# FX_MCU.net
KiCad netlist of a schematic drawn in Altium Designer
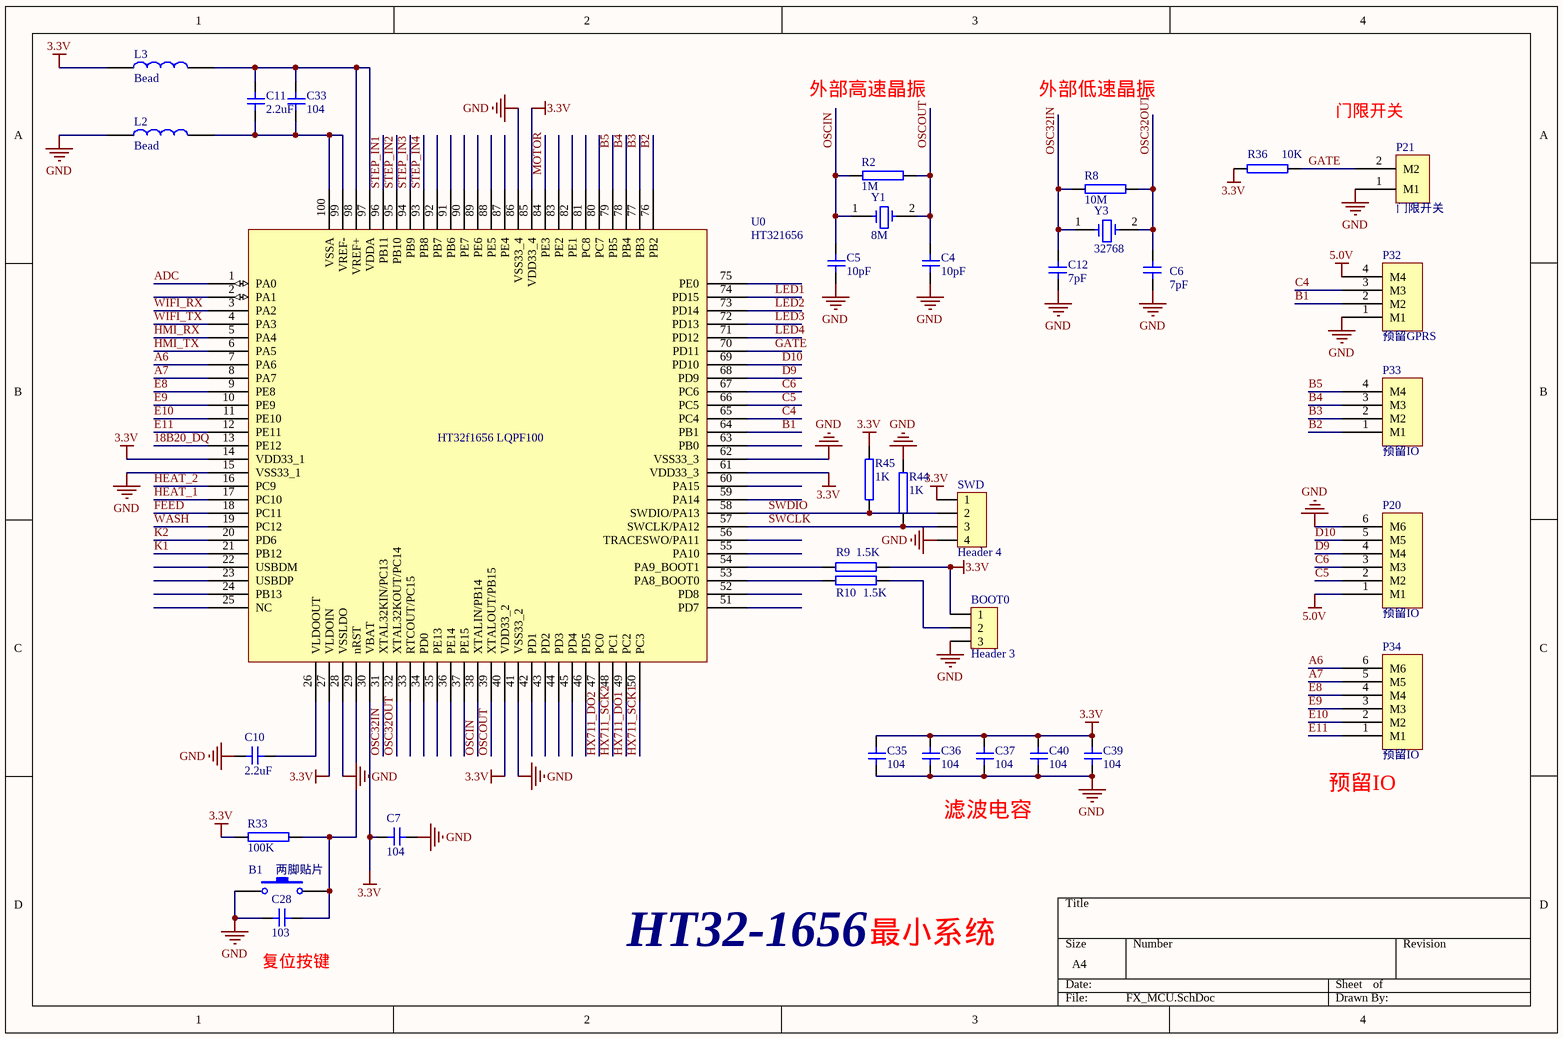
[diagram p0: FX_MCU.SchDoc]

(export (version "E")
  (design (tool "Eeschema 10.0.6"))
  (components
    (comp (ref "B1") (value "两脚贴片") (footprint "贴片按键") (libsource (lib "窝牛器件封装") (part "Key(两脚贴片)")))
    (comp (ref "BOOT0")
      (value "Header 3")
      (footprint "Header 3")
      (libsource (lib "窝牛器件封装") (part "Header 3"))
    )
    (comp (ref "C4") (value "10pF") (footprint "0805C") (libsource (lib "窝牛器件封装") (part "C1")))
    (comp (ref "C5") (value "10pF") (footprint "0805C") (libsource (lib "窝牛器件封装") (part "C1")))
    (comp (ref "C6") (value "7pF") (footprint "0805C") (libsource (lib "窝牛器件封装") (part "C1")))
    (comp (ref "C7") (value "104") (footprint "0805C") (libsource (lib "窝牛器件封装") (part "C1")))
    (comp (ref "C10") (value "2.2uF") (footprint "0805C") (libsource (lib "窝牛器件封装") (part "C1")))
    (comp (ref "C11") (value "2.2uF") (footprint "0805C") (libsource (lib "窝牛器件封装") (part "C1")))
    (comp (ref "C12") (value "7pF") (footprint "0805C") (libsource (lib "窝牛器件封装") (part "C1")))
    (comp (ref "C28") (value "103") (footprint "0805C") (libsource (lib "窝牛器件封装") (part "C1")))
    (comp (ref "C33") (value "104") (footprint "0805C") (libsource (lib "窝牛器件封装") (part "C1")))
    (comp (ref "C35") (value "104") (footprint "0805C") (libsource (lib "窝牛器件封装") (part "C1")))
    (comp (ref "C36") (value "104") (footprint "0805C") (libsource (lib "窝牛器件封装") (part "C1")))
    (comp (ref "C37") (value "104") (footprint "0805C") (libsource (lib "窝牛器件封装") (part "C1")))
    (comp (ref "C39") (value "104") (footprint "0805C") (libsource (lib "窝牛器件封装") (part "C1")))
    (comp (ref "C40") (value "104") (footprint "0805C") (libsource (lib "窝牛器件封装") (part "C1")))
    (comp (ref "L2") (value "Bead") (footprint "0805L") (libsource (lib "窝牛器件封装") (part "L1")))
    (comp (ref "L3") (value "Bead") (footprint "0805L") (libsource (lib "窝牛器件封装") (part "L1")))
    (comp (ref "P20")
      (value "预留IO")
      (footprint "接线端子(小)-6PIN")
      (libsource (lib "窝牛器件封装") (part "接线端子(小)-6PIN"))
    )
    (comp (ref "P21")
      (value "门限开关")
      (footprint "接线端子(小)-2PIN")
      (libsource (lib "窝牛器件封装") (part "接线端子(小)-2PIN"))
    )
    (comp (ref "P32")
      (value "预留GPRS")
      (footprint "接线端子(小)-4PIN")
      (libsource (lib "窝牛器件封装") (part "接线端子(小)-4PIN"))
    )
    (comp (ref "P33")
      (value "预留IO")
      (footprint "接线端子(小)-4PIN")
      (libsource (lib "窝牛器件封装") (part "接线端子(小)-4PIN"))
    )
    (comp (ref "P34")
      (value "预留IO")
      (footprint "接线端子(小)-6PIN")
      (libsource (lib "窝牛器件封装") (part "接线端子(小)-6PIN"))
    )
    (comp (ref "R2") (value "1M") (footprint "0805R") (libsource (lib "窝牛器件封装") (part "R1")))
    (comp (ref "R8") (value "10M") (footprint "0805R") (libsource (lib "窝牛器件封装") (part "R1")))
    (comp (ref "R9") (value "1.5K") (footprint "0805R") (libsource (lib "窝牛器件封装") (part "R1")))
    (comp (ref "R10") (value "1.5K") (footprint "0805R") (libsource (lib "窝牛器件封装") (part "R1")))
    (comp (ref "R33") (value "100K") (footprint "0805R") (libsource (lib "窝牛器件封装") (part "R1")))
    (comp (ref "R36") (value "10K") (footprint "0805R") (libsource (lib "窝牛器件封装") (part "R1")))
    (comp (ref "R44") (value "1K") (footprint "0805R") (libsource (lib "窝牛器件封装") (part "R1")))
    (comp (ref "R45") (value "1K") (footprint "0805R") (libsource (lib "窝牛器件封装") (part "R1")))
    (comp (ref "SWD") (value "Header 4") (footprint "Header 4") (libsource (lib "窝牛器件封装") (part "Header 4")))
    (comp (ref "U0") (value "HT321656") (footprint "LQFP100") (libsource (lib "devil") (part "HT321656")))
    (comp (ref "Y1") (value "8M") (footprint "22M(晶振)") (libsource (lib "窝牛器件封装") (part "XTAL")))
    (comp (ref "Y3") (value "32768") (footprint "XTAL") (libsource (lib "窝牛器件封装") (part "XTAL")))
  )
  (nets
    (net (code "1") (name "/18B20_DQ") (class "Default")
      (node (ref "U0") (pin "13") (pinfunction "PE12_13") (pintype "passive"))
    )
    (net (code "2") (name "/A6") (class "Default")
      (node (ref "P34") (pin "6") (pinfunction "M6_6") (pintype "passive"))
      (node (ref "U0") (pin "7") (pinfunction "PA6_7") (pintype "passive"))
    )
    (net (code "3") (name "/A7") (class "Default")
      (node (ref "P34") (pin "5") (pinfunction "M5_5") (pintype "passive"))
      (node (ref "U0") (pin "8") (pinfunction "PA7_8") (pintype "passive"))
    )
    (net (code "4") (name "/ADC") (class "Default")
      (node (ref "U0") (pin "1") (pinfunction "PA0_1") (pintype "bidirectional"))
    )
    (net (code "5") (name "/B1") (class "Default")
      (node (ref "P32") (pin "2") (pinfunction "M2_2") (pintype "passive"))
      (node (ref "U0") (pin "64") (pinfunction "PB1_64") (pintype "passive"))
    )
    (net (code "6") (name "/B2") (class "Default")
      (node (ref "P33") (pin "1") (pinfunction "M1_1") (pintype "passive"))
      (node (ref "U0") (pin "76") (pinfunction "PB2_76") (pintype "passive"))
    )
    (net (code "7") (name "/B3") (class "Default")
      (node (ref "P33") (pin "2") (pinfunction "M2_2") (pintype "passive"))
      (node (ref "U0") (pin "77") (pinfunction "PB3_77") (pintype "passive"))
    )
    (net (code "8") (name "/B4") (class "Default")
      (node (ref "P33") (pin "3") (pinfunction "M3_3") (pintype "passive"))
      (node (ref "U0") (pin "78") (pinfunction "PB4_78") (pintype "passive"))
    )
    (net (code "9") (name "/B5") (class "Default")
      (node (ref "P33") (pin "4") (pinfunction "M4_4") (pintype "passive"))
      (node (ref "U0") (pin "79") (pinfunction "PB5_79") (pintype "passive"))
    )
    (net (code "10") (name "/C4") (class "Default")
      (node (ref "P32") (pin "3") (pinfunction "M3_3") (pintype "passive"))
      (node (ref "U0") (pin "65") (pinfunction "PC4_65") (pintype "passive"))
    )
    (net (code "11") (name "/C5") (class "Default")
      (node (ref "P20") (pin "2") (pinfunction "M2_2") (pintype "passive"))
      (node (ref "U0") (pin "66") (pinfunction "PC5_66") (pintype "passive"))
    )
    (net (code "12") (name "/C6") (class "Default")
      (node (ref "P20") (pin "3") (pinfunction "M3_3") (pintype "passive"))
      (node (ref "U0") (pin "67") (pinfunction "PC6_67") (pintype "passive"))
    )
    (net (code "13") (name "/D9") (class "Default")
      (node (ref "P20") (pin "4") (pinfunction "M4_4") (pintype "passive"))
      (node (ref "U0") (pin "68") (pinfunction "PD9_68") (pintype "passive"))
    )
    (net (code "14") (name "/D10") (class "Default")
      (node (ref "P20") (pin "5") (pinfunction "M5_5") (pintype "passive"))
      (node (ref "U0") (pin "69") (pinfunction "PD10_69") (pintype "passive"))
    )
    (net (code "15") (name "/E8") (class "Default")
      (node (ref "P34") (pin "4") (pinfunction "M4_4") (pintype "passive"))
      (node (ref "U0") (pin "9") (pinfunction "PE8_9") (pintype "passive"))
    )
    (net (code "16") (name "/E9") (class "Default")
      (node (ref "P34") (pin "3") (pinfunction "M3_3") (pintype "passive"))
      (node (ref "U0") (pin "10") (pinfunction "PE9_10") (pintype "passive"))
    )
    (net (code "17") (name "/E10") (class "Default")
      (node (ref "P34") (pin "2") (pinfunction "M2_2") (pintype "passive"))
      (node (ref "U0") (pin "11") (pinfunction "PE10_11") (pintype "passive"))
    )
    (net (code "18") (name "/E11") (class "Default")
      (node (ref "P34") (pin "1") (pinfunction "M1_1") (pintype "passive"))
      (node (ref "U0") (pin "12") (pinfunction "PE11_12") (pintype "passive"))
    )
    (net (code "19") (name "/FEED") (class "Default")
      (node (ref "U0") (pin "18") (pinfunction "PC11_18") (pintype "passive"))
    )
    (net (code "20") (name "/GATE") (class "Default")
      (node (ref "P21") (pin "2") (pinfunction "M2_2") (pintype "passive"))
      (node (ref "R36") (pin "2") (pinfunction "2_2") (pintype "passive"))
      (node (ref "U0") (pin "70") (pinfunction "PD11_70") (pintype "passive"))
    )
    (net (code "21") (name "/HEAT_1") (class "Default")
      (node (ref "U0") (pin "17") (pinfunction "PC10_17") (pintype "passive"))
    )
    (net (code "22") (name "/HEAT_2") (class "Default")
      (node (ref "U0") (pin "16") (pinfunction "PC9_16") (pintype "passive"))
    )
    (net (code "23") (name "/HMI_RX") (class "Default")
      (node (ref "U0") (pin "5") (pinfunction "PA4_5") (pintype "passive"))
    )
    (net (code "24") (name "/HMI_TX") (class "Default")
      (node (ref "U0") (pin "6") (pinfunction "PA5_6") (pintype "passive"))
    )
    (net (code "25") (name "/HX711_DO1") (class "Default")
      (node (ref "U0") (pin "49") (pinfunction "PC2_49") (pintype "passive"))
    )
    (net (code "26") (name "/HX711_DO2") (class "Default")
      (node (ref "U0") (pin "47") (pinfunction "PC0_47") (pintype "passive"))
    )
    (net (code "27") (name "/HX711_SCK1") (class "Default")
      (node (ref "U0") (pin "50") (pinfunction "PC3_50") (pintype "passive"))
    )
    (net (code "28") (name "/HX711_SCK2") (class "Default")
      (node (ref "U0") (pin "48") (pinfunction "PC1_48") (pintype "passive"))
    )
    (net (code "29") (name "/K1") (class "Default")
      (node (ref "U0") (pin "21") (pinfunction "PB12_21") (pintype "passive"))
    )
    (net (code "30") (name "/K2") (class "Default")
      (node (ref "U0") (pin "20") (pinfunction "PD6_20") (pintype "passive"))
    )
    (net (code "31") (name "/LED1") (class "Default")
      (node (ref "U0") (pin "74") (pinfunction "PD15_74") (pintype "passive"))
    )
    (net (code "32") (name "/LED2") (class "Default")
      (node (ref "U0") (pin "73") (pinfunction "PD14_73") (pintype "passive"))
    )
    (net (code "33") (name "/LED3") (class "Default")
      (node (ref "U0") (pin "72") (pinfunction "PD13_72") (pintype "passive"))
    )
    (net (code "34") (name "/LED4") (class "Default")
      (node (ref "U0") (pin "71") (pinfunction "PD12_71") (pintype "passive"))
    )
    (net (code "35") (name "/MOTOR") (class "Default")
      (node (ref "U0") (pin "84") (pinfunction "PE3_84") (pintype "passive"))
    )
    (net (code "36") (name "/OSC32IN") (class "Default")
      (node (ref "C12") (pin "1") (pinfunction "1_1") (pintype "passive"))
      (node (ref "R8") (pin "1") (pinfunction "1_1") (pintype "passive"))
      (node (ref "U0") (pin "31") (pinfunction "XTAL32KIN/PC13_31") (pintype "passive"))
      (node (ref "Y3") (pin "1") (pinfunction "1_1") (pintype "passive"))
    )
    (net (code "37") (name "/OSC32OUT") (class "Default")
      (node (ref "C6") (pin "1") (pinfunction "1_1") (pintype "passive"))
      (node (ref "R8") (pin "2") (pinfunction "2_2") (pintype "passive"))
      (node (ref "U0") (pin "32") (pinfunction "XTAL32KOUT/PC14_32") (pintype "passive"))
      (node (ref "Y3") (pin "2") (pinfunction "2_2") (pintype "passive"))
    )
    (net (code "38") (name "/OSCIN") (class "Default")
      (node (ref "C5") (pin "2") (pinfunction "2_2") (pintype "passive"))
      (node (ref "R2") (pin "1") (pinfunction "1_1") (pintype "passive"))
      (node (ref "U0") (pin "38") (pinfunction "XTALIN/PB14_38") (pintype "passive"))
      (node (ref "Y1") (pin "1") (pinfunction "1_1") (pintype "passive"))
    )
    (net (code "39") (name "/OSCOUT") (class "Default")
      (node (ref "C4") (pin "2") (pinfunction "2_2") (pintype "passive"))
      (node (ref "R2") (pin "2") (pinfunction "2_2") (pintype "passive"))
      (node (ref "U0") (pin "39") (pinfunction "XTALOUT/PB15_39") (pintype "passive"))
      (node (ref "Y1") (pin "2") (pinfunction "2_2") (pintype "passive"))
    )
    (net (code "40") (name "/STEP_IN1") (class "Default")
      (node (ref "U0") (pin "96") (pinfunction "PB11_96") (pintype "passive"))
    )
    (net (code "41") (name "/STEP_IN2") (class "Default")
      (node (ref "U0") (pin "95") (pinfunction "PB10_95") (pintype "passive"))
    )
    (net (code "42") (name "/STEP_IN3") (class "Default")
      (node (ref "U0") (pin "94") (pinfunction "PB9_94") (pintype "passive"))
    )
    (net (code "43") (name "/STEP_IN4") (class "Default")
      (node (ref "U0") (pin "93") (pinfunction "PB8_93") (pintype "passive"))
    )
    (net (code "44") (name "/SWCLK") (class "Default")
      (node (ref "R44") (pin "1") (pinfunction "1_1") (pintype "passive"))
      (node (ref "SWD") (pin "3") (pinfunction "3_3") (pintype "passive"))
      (node (ref "U0") (pin "57") (pinfunction "SWCLK/PA12_57") (pintype "passive"))
    )
    (net (code "45") (name "/SWDIO") (class "Default")
      (node (ref "R45") (pin "1") (pinfunction "1_1") (pintype "passive"))
      (node (ref "SWD") (pin "2") (pinfunction "2_2") (pintype "passive"))
      (node (ref "U0") (pin "58") (pinfunction "SWDIO/PA13_58") (pintype "passive"))
    )
    (net (code "46") (name "/WASH") (class "Default")
      (node (ref "U0") (pin "19") (pinfunction "PC12_19") (pintype "passive"))
    )
    (net (code "47") (name "/WIFI_RX") (class "Default")
      (node (ref "U0") (pin "3") (pinfunction "PA2_3") (pintype "passive"))
    )
    (net (code "48") (name "/WIFI_TX") (class "Default")
      (node (ref "U0") (pin "4") (pinfunction "PA3_4") (pintype "passive"))
    )
    (net (code "49") (name "3.3V") (class "Default")
      (node (ref "BOOT0") (pin "1") (pinfunction "1_1") (pintype "passive"))
      (node (ref "C35") (pin "2") (pinfunction "2_2") (pintype "passive"))
      (node (ref "C36") (pin "2") (pinfunction "2_2") (pintype "passive"))
      (node (ref "C37") (pin "2") (pinfunction "2_2") (pintype "passive"))
      (node (ref "C39") (pin "2") (pinfunction "2_2") (pintype "passive"))
      (node (ref "C40") (pin "2") (pinfunction "2_2") (pintype "passive"))
      (node (ref "C7") (pin "2") (pinfunction "2_2") (pintype "passive"))
      (node (ref "L3") (pin "1") (pinfunction "1_1") (pintype "passive"))
      (node (ref "R33") (pin "1") (pinfunction "1_1") (pintype "passive"))
      (node (ref "R36") (pin "1") (pinfunction "1_1") (pintype "passive"))
      (node (ref "R45") (pin "2") (pinfunction "2_2") (pintype "passive"))
      (node (ref "R9") (pin "2") (pinfunction "2_2") (pintype "passive"))
      (node (ref "SWD") (pin "1") (pinfunction "1_1") (pintype "passive"))
      (node (ref "U0") (pin "14") (pinfunction "VDD33_1_14") (pintype "passive"))
      (node (ref "U0") (pin "27") (pinfunction "VLDOIN_27") (pintype "passive"))
      (node (ref "U0") (pin "30") (pinfunction "VBAT_30") (pintype "passive"))
      (node (ref "U0") (pin "40") (pinfunction "VDD33_2_40") (pintype "passive"))
      (node (ref "U0") (pin "61") (pinfunction "VDD33_3_61") (pintype "passive"))
      (node (ref "U0") (pin "85") (pinfunction "VDD33_4_85") (pintype "passive"))
    )
    (net (code "50") (name "5.0V") (class "Default")
      (node (ref "P20") (pin "1") (pinfunction "M1_1") (pintype "passive"))
      (node (ref "P32") (pin "4") (pinfunction "M4_4") (pintype "passive"))
    )
    (net (code "51") (name "GND") (class "Default")
      (node (ref "B1") (pin "1") (pinfunction "1_1") (pintype "passive"))
      (node (ref "BOOT0") (pin "3") (pinfunction "3_3") (pintype "passive"))
      (node (ref "C10") (pin "2") (pinfunction "2_2") (pintype "passive"))
      (node (ref "C12") (pin "2") (pinfunction "2_2") (pintype "passive"))
      (node (ref "C28") (pin "2") (pinfunction "2_2") (pintype "passive"))
      (node (ref "C35") (pin "1") (pinfunction "1_1") (pintype "passive"))
      (node (ref "C36") (pin "1") (pinfunction "1_1") (pintype "passive"))
      (node (ref "C37") (pin "1") (pinfunction "1_1") (pintype "passive"))
      (node (ref "C39") (pin "1") (pinfunction "1_1") (pintype "passive"))
      (node (ref "C4") (pin "1") (pinfunction "1_1") (pintype "passive"))
      (node (ref "C40") (pin "1") (pinfunction "1_1") (pintype "passive"))
      (node (ref "C5") (pin "1") (pinfunction "1_1") (pintype "passive"))
      (node (ref "C6") (pin "2") (pinfunction "2_2") (pintype "passive"))
      (node (ref "C7") (pin "1") (pinfunction "1_1") (pintype "passive"))
      (node (ref "L2") (pin "1") (pinfunction "1_1") (pintype "passive"))
      (node (ref "P20") (pin "6") (pinfunction "M6_6") (pintype "passive"))
      (node (ref "P21") (pin "1") (pinfunction "M1_1") (pintype "passive"))
      (node (ref "P32") (pin "1") (pinfunction "M1_1") (pintype "passive"))
      (node (ref "R44") (pin "2") (pinfunction "2_2") (pintype "passive"))
      (node (ref "SWD") (pin "4") (pinfunction "4_4") (pintype "passive"))
      (node (ref "U0") (pin "15") (pinfunction "VSS33_1_15") (pintype "passive"))
      (node (ref "U0") (pin "28") (pinfunction "VSSLDO_28") (pintype "passive"))
      (node (ref "U0") (pin "41") (pinfunction "VSS33_2_41") (pintype "passive"))
      (node (ref "U0") (pin "62") (pinfunction "VSS33_3_62") (pintype "passive"))
      (node (ref "U0") (pin "86") (pinfunction "VSS33_4_86") (pintype "passive"))
    )
    (net (code "52") (name "Net-(BOOT0-Pad2)") (class "Default")
      (node (ref "BOOT0") (pin "2") (pinfunction "2_2") (pintype "passive"))
      (node (ref "R10") (pin "2") (pinfunction "2_2") (pintype "passive"))
    )
    (net (code "53") (name "Net-(U0-PA8_BOOT0)") (class "Default")
      (node (ref "R10") (pin "1") (pinfunction "1_1") (pintype "passive"))
      (node (ref "U0") (pin "53") (pinfunction "PA8_BOOT0_53") (pintype "passive"))
    )
    (net (code "54") (name "Net-(U0-PA9_BOOT1)") (class "Default")
      (node (ref "R9") (pin "1") (pinfunction "1_1") (pintype "passive"))
      (node (ref "U0") (pin "54") (pinfunction "PA9_BOOT1_54") (pintype "passive"))
    )
    (net (code "55") (name "Net-(U0-VDDA)") (class "Default")
      (node (ref "C11") (pin "2") (pinfunction "2_2") (pintype "passive"))
      (node (ref "C33") (pin "2") (pinfunction "2_2") (pintype "passive"))
      (node (ref "L3") (pin "2") (pinfunction "2_2") (pintype "passive"))
      (node (ref "U0") (pin "97") (pinfunction "VDDA_97") (pintype "passive"))
      (node (ref "U0") (pin "98") (pinfunction "VREF+_98") (pintype "passive"))
    )
    (net (code "56") (name "Net-(U0-VLDOOUT)") (class "Default")
      (node (ref "C10") (pin "1") (pinfunction "1_1") (pintype "passive"))
      (node (ref "U0") (pin "26") (pinfunction "VLDOOUT_26") (pintype "passive"))
    )
    (net (code "57") (name "Net-(U0-VREF-)") (class "Default")
      (node (ref "C11") (pin "1") (pinfunction "1_1") (pintype "passive"))
      (node (ref "C33") (pin "1") (pinfunction "1_1") (pintype "passive"))
      (node (ref "L2") (pin "2") (pinfunction "2_2") (pintype "passive"))
      (node (ref "U0") (pin "100") (pinfunction "VSSA_100") (pintype "passive"))
      (node (ref "U0") (pin "99") (pinfunction "VREF-_99") (pintype "passive"))
    )
    (net (code "58") (name "Net-(U0-nRST)") (class "Default")
      (node (ref "B1") (pin "2") (pinfunction "2_2") (pintype "passive"))
      (node (ref "C28") (pin "1") (pinfunction "1_1") (pintype "passive"))
      (node (ref "R33") (pin "2") (pinfunction "2_2") (pintype "passive"))
      (node (ref "U0") (pin "29") (pinfunction "nRST_29") (pintype "passive"))
    )
    (net (code "59") (name "unconnected-(U0-NC-Pad25)") (class "Default")
      (node (ref "U0") (pin "25") (pinfunction "NC_25") (pintype "passive"))
    )
    (net (code "60") (name "unconnected-(U0-PA1-Pad2)") (class "Default")
      (node (ref "U0") (pin "2") (pinfunction "PA1_2") (pintype "bidirectional"))
    )
    (net (code "61") (name "unconnected-(U0-PA10-Pad55)") (class "Default")
      (node (ref "U0") (pin "55") (pinfunction "PA10_55") (pintype "passive"))
    )
    (net (code "62") (name "unconnected-(U0-PA14-Pad59)") (class "Default")
      (node (ref "U0") (pin "59") (pinfunction "PA14_59") (pintype "passive"))
    )
    (net (code "63") (name "unconnected-(U0-PA15-Pad60)") (class "Default")
      (node (ref "U0") (pin "60") (pinfunction "PA15_60") (pintype "passive"))
    )
    (net (code "64") (name "unconnected-(U0-PB0-Pad63)") (class "Default")
      (node (ref "U0") (pin "63") (pinfunction "PB0_63") (pintype "passive"))
    )
    (net (code "65") (name "unconnected-(U0-PB6-Pad91)") (class "Default")
      (node (ref "U0") (pin "91") (pinfunction "PB6_91") (pintype "passive"))
    )
    (net (code "66") (name "unconnected-(U0-PB7-Pad92)") (class "Default")
      (node (ref "U0") (pin "92") (pinfunction "PB7_92") (pintype "passive"))
    )
    (net (code "67") (name "unconnected-(U0-PB13-Pad24)") (class "Default")
      (node (ref "U0") (pin "24") (pinfunction "PB13_24") (pintype "passive"))
    )
    (net (code "68") (name "unconnected-(U0-PC7-Pad80)") (class "Default")
      (node (ref "U0") (pin "80") (pinfunction "PC7_80") (pintype "passive"))
    )
    (net (code "69") (name "unconnected-(U0-PC8-Pad81)") (class "Default")
      (node (ref "U0") (pin "81") (pinfunction "PC8_81") (pintype "passive"))
    )
    (net (code "70") (name "unconnected-(U0-PD0-Pad34)") (class "Default")
      (node (ref "U0") (pin "34") (pinfunction "PD0_34") (pintype "passive"))
    )
    (net (code "71") (name "unconnected-(U0-PD1-Pad42)") (class "Default")
      (node (ref "U0") (pin "42") (pinfunction "PD1_42") (pintype "passive"))
    )
    (net (code "72") (name "unconnected-(U0-PD2-Pad43)") (class "Default")
      (node (ref "U0") (pin "43") (pinfunction "PD2_43") (pintype "passive"))
    )
    (net (code "73") (name "unconnected-(U0-PD3-Pad44)") (class "Default")
      (node (ref "U0") (pin "44") (pinfunction "PD3_44") (pintype "passive"))
    )
    (net (code "74") (name "unconnected-(U0-PD4-Pad45)") (class "Default")
      (node (ref "U0") (pin "45") (pinfunction "PD4_45") (pintype "passive"))
    )
    (net (code "75") (name "unconnected-(U0-PD5-Pad46)") (class "Default")
      (node (ref "U0") (pin "46") (pinfunction "PD5_46") (pintype "passive"))
    )
    (net (code "76") (name "unconnected-(U0-PD7-Pad51)") (class "Default")
      (node (ref "U0") (pin "51") (pinfunction "PD7_51") (pintype "passive"))
    )
    (net (code "77") (name "unconnected-(U0-PD8-Pad52)") (class "Default")
      (node (ref "U0") (pin "52") (pinfunction "PD8_52") (pintype "passive"))
    )
    (net (code "78") (name "unconnected-(U0-PE0-Pad75)") (class "Default")
      (node (ref "U0") (pin "75") (pinfunction "PE0_75") (pintype "passive"))
    )
    (net (code "79") (name "unconnected-(U0-PE1-Pad82)") (class "Default")
      (node (ref "U0") (pin "82") (pinfunction "PE1_82") (pintype "passive"))
    )
    (net (code "80") (name "unconnected-(U0-PE2-Pad83)") (class "Default")
      (node (ref "U0") (pin "83") (pinfunction "PE2_83") (pintype "passive"))
    )
    (net (code "81") (name "unconnected-(U0-PE4-Pad87)") (class "Default")
      (node (ref "U0") (pin "87") (pinfunction "PE4_87") (pintype "passive"))
    )
    (net (code "82") (name "unconnected-(U0-PE5-Pad88)") (class "Default")
      (node (ref "U0") (pin "88") (pinfunction "PE5_88") (pintype "passive"))
    )
    (net (code "83") (name "unconnected-(U0-PE6-Pad89)") (class "Default")
      (node (ref "U0") (pin "89") (pinfunction "PE6_89") (pintype "passive"))
    )
    (net (code "84") (name "unconnected-(U0-PE7-Pad90)") (class "Default")
      (node (ref "U0") (pin "90") (pinfunction "PE7_90") (pintype "passive"))
    )
    (net (code "85") (name "unconnected-(U0-PE13-Pad35)") (class "Default")
      (node (ref "U0") (pin "35") (pinfunction "PE13_35") (pintype "passive"))
    )
    (net (code "86") (name "unconnected-(U0-PE14-Pad36)") (class "Default")
      (node (ref "U0") (pin "36") (pinfunction "PE14_36") (pintype "passive"))
    )
    (net (code "87") (name "unconnected-(U0-PE15-Pad37)") (class "Default")
      (node (ref "U0") (pin "37") (pinfunction "PE15_37") (pintype "passive"))
    )
    (net (code "88") (name "unconnected-(U0-RTCOUT{slash}PC15-Pad33)") (class "Default")
      (node (ref "U0") (pin "33") (pinfunction "RTCOUT/PC15_33") (pintype "passive"))
    )
    (net (code "89") (name "unconnected-(U0-TRACESWO{slash}PA11-Pad56)") (class "Default")
      (node (ref "U0") (pin "56") (pinfunction "TRACESWO/PA11_56") (pintype "passive"))
    )
    (net (code "90") (name "unconnected-(U0-USBDM-Pad22)") (class "Default")
      (node (ref "U0") (pin "22") (pinfunction "USBDM_22") (pintype "passive"))
    )
    (net (code "91") (name "unconnected-(U0-USBDP-Pad23)") (class "Default")
      (node (ref "U0") (pin "23") (pinfunction "USBDP_23") (pintype "passive"))
    )
  )
)
